# main.net
KiCad netlist of a schematic drawn in Altium Designer
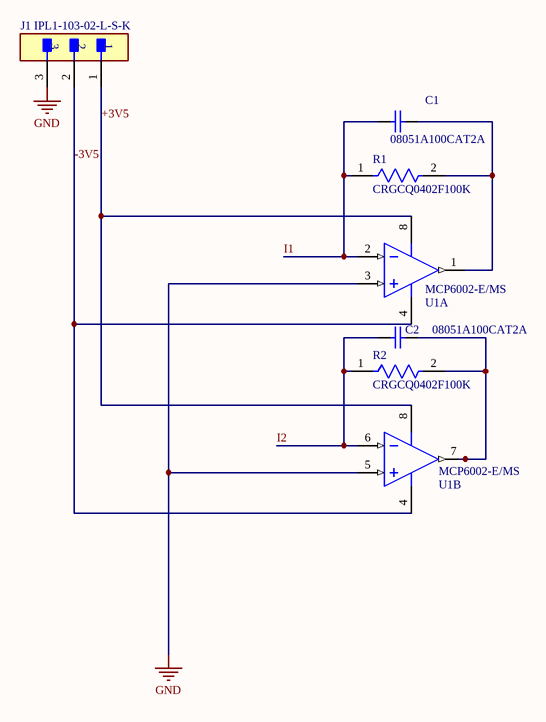
[diagram p0: main.SchDoc]

(export (version "E")
  (design (tool "Eeschema 10.0.6"))
  (components
    (comp (ref "C1")
      (value "08051A100CAT2A")
      (footprint "CAPC2013X94X50NL20T25")
      (fields (field (name "MANUFACTURER") "AVX Interconnect / Elco"))
      (libsource (lib "Altium Content Vault") (part "CAP"))
    )
    (comp (ref "C2")
      (value "08051A100CAT2A")
      (footprint "CAPC2013X94X50NL20T25")
      (fields (field (name "MANUFACTURER") "AVX Interconnect / Elco"))
      (libsource (lib "Altium Content Vault") (part "CAP"))
    )
    (comp (ref "J1")
      (value "IPL1-103-02-L-S-K")
      (footprint "FP-IPL1-103-02-L-S-K-0")
      (description "3 Position 1 Row .100\" (2.54 mm) pitch connector")
      (libsource (lib "Altium Content Vault") (part "044adefd6287a37253661db429b75cc"))
    )
    (comp (ref "R1")
      (value "CRGCQ0402F100K")
      (footprint "FP-CRGCQ0402-IPC_C")
      (description "CRGCQ0402 100KΩ 1% ±100ppm/°C 50V")
      (fields
        (field (name "TOLERANCE") "0.01")
        (field (name "OCTOPART") "https://octopart.com/crgcq0402f100k-te+connectivity-91017930")
      )
      (libsource (lib "Altium Content Vault") (part "1029c3af85768c4190bb7ad29bc67b5"))
    )
    (comp (ref "R2")
      (value "CRGCQ0402F100K")
      (footprint "FP-CRGCQ0402-IPC_C")
      (description "CRGCQ0402 100KΩ 1% ±100ppm/°C 50V")
      (fields
        (field (name "TOLERANCE") "0.01")
        (field (name "OCTOPART") "https://octopart.com/crgcq0402f100k-te+connectivity-91017930")
      )
      (libsource (lib "Altium Content Vault") (part "1029c3af85768c4190bb7ad29bc67b5"))
    )
    (comp (ref "U1")
      (value "MCP6002-E/MS")
      (footprint "MSOP-MS8_M")
      (description "None")
      (libsource (lib "Altium Content Vault") (part "AMP-OPA-MCP6002-IL8"))
    )
  )
  (nets
    (net (code "1") (name "/+3V5") (class "Default")
      (node (ref "J1") (pin "1") (pinfunction "1_1") (pintype "passive"))
      (node (ref "U1") (pin "8") (pinfunction "VDD_8") (pintype "power_in"))
    )
    (net (code "2") (name "/-3V5") (class "Default")
      (node (ref "J1") (pin "2") (pinfunction "2_2") (pintype "passive"))
      (node (ref "U1") (pin "4") (pinfunction "VSS_4") (pintype "power_in"))
    )
    (net (code "3") (name "/I1") (class "Default")
      (node (ref "C1") (pin "1") (pinfunction "1_1") (pintype "passive"))
      (node (ref "R1") (pin "1") (pinfunction "1_1") (pintype "passive"))
      (node (ref "U1") (pin "2") (pinfunction "VINA-_2") (pintype "input"))
    )
    (net (code "4") (name "/I2") (class "Default")
      (node (ref "C2") (pin "1") (pinfunction "1_1") (pintype "passive"))
      (node (ref "R2") (pin "1") (pinfunction "1_1") (pintype "passive"))
      (node (ref "U1") (pin "6") (pinfunction "VINB-_6") (pintype "input"))
    )
    (net (code "5") (name "GND") (class "Default")
      (node (ref "J1") (pin "3") (pinfunction "3_3") (pintype "passive"))
      (node (ref "U1") (pin "3") (pinfunction "VINA+_3") (pintype "input"))
      (node (ref "U1") (pin "5") (pinfunction "VINB+_5") (pintype "input"))
    )
    (net (code "6") (name "Net-(U1A-VOUTA)") (class "Default")
      (node (ref "C1") (pin "2") (pinfunction "2_2") (pintype "passive"))
      (node (ref "R1") (pin "2") (pinfunction "2_2") (pintype "passive"))
      (node (ref "U1") (pin "1") (pinfunction "VOUTA_1") (pintype "output"))
    )
    (net (code "7") (name "Net-(U1B-VOUTB)") (class "Default")
      (node (ref "C2") (pin "2") (pinfunction "2_2") (pintype "passive"))
      (node (ref "R2") (pin "2") (pinfunction "2_2") (pintype "passive"))
      (node (ref "U1") (pin "7") (pinfunction "VOUTB_7") (pintype "output"))
    )
  )
)
